# Trigger_Sequencer_build_tested.net
KiCad netlist of a schematic drawn in EAGLE
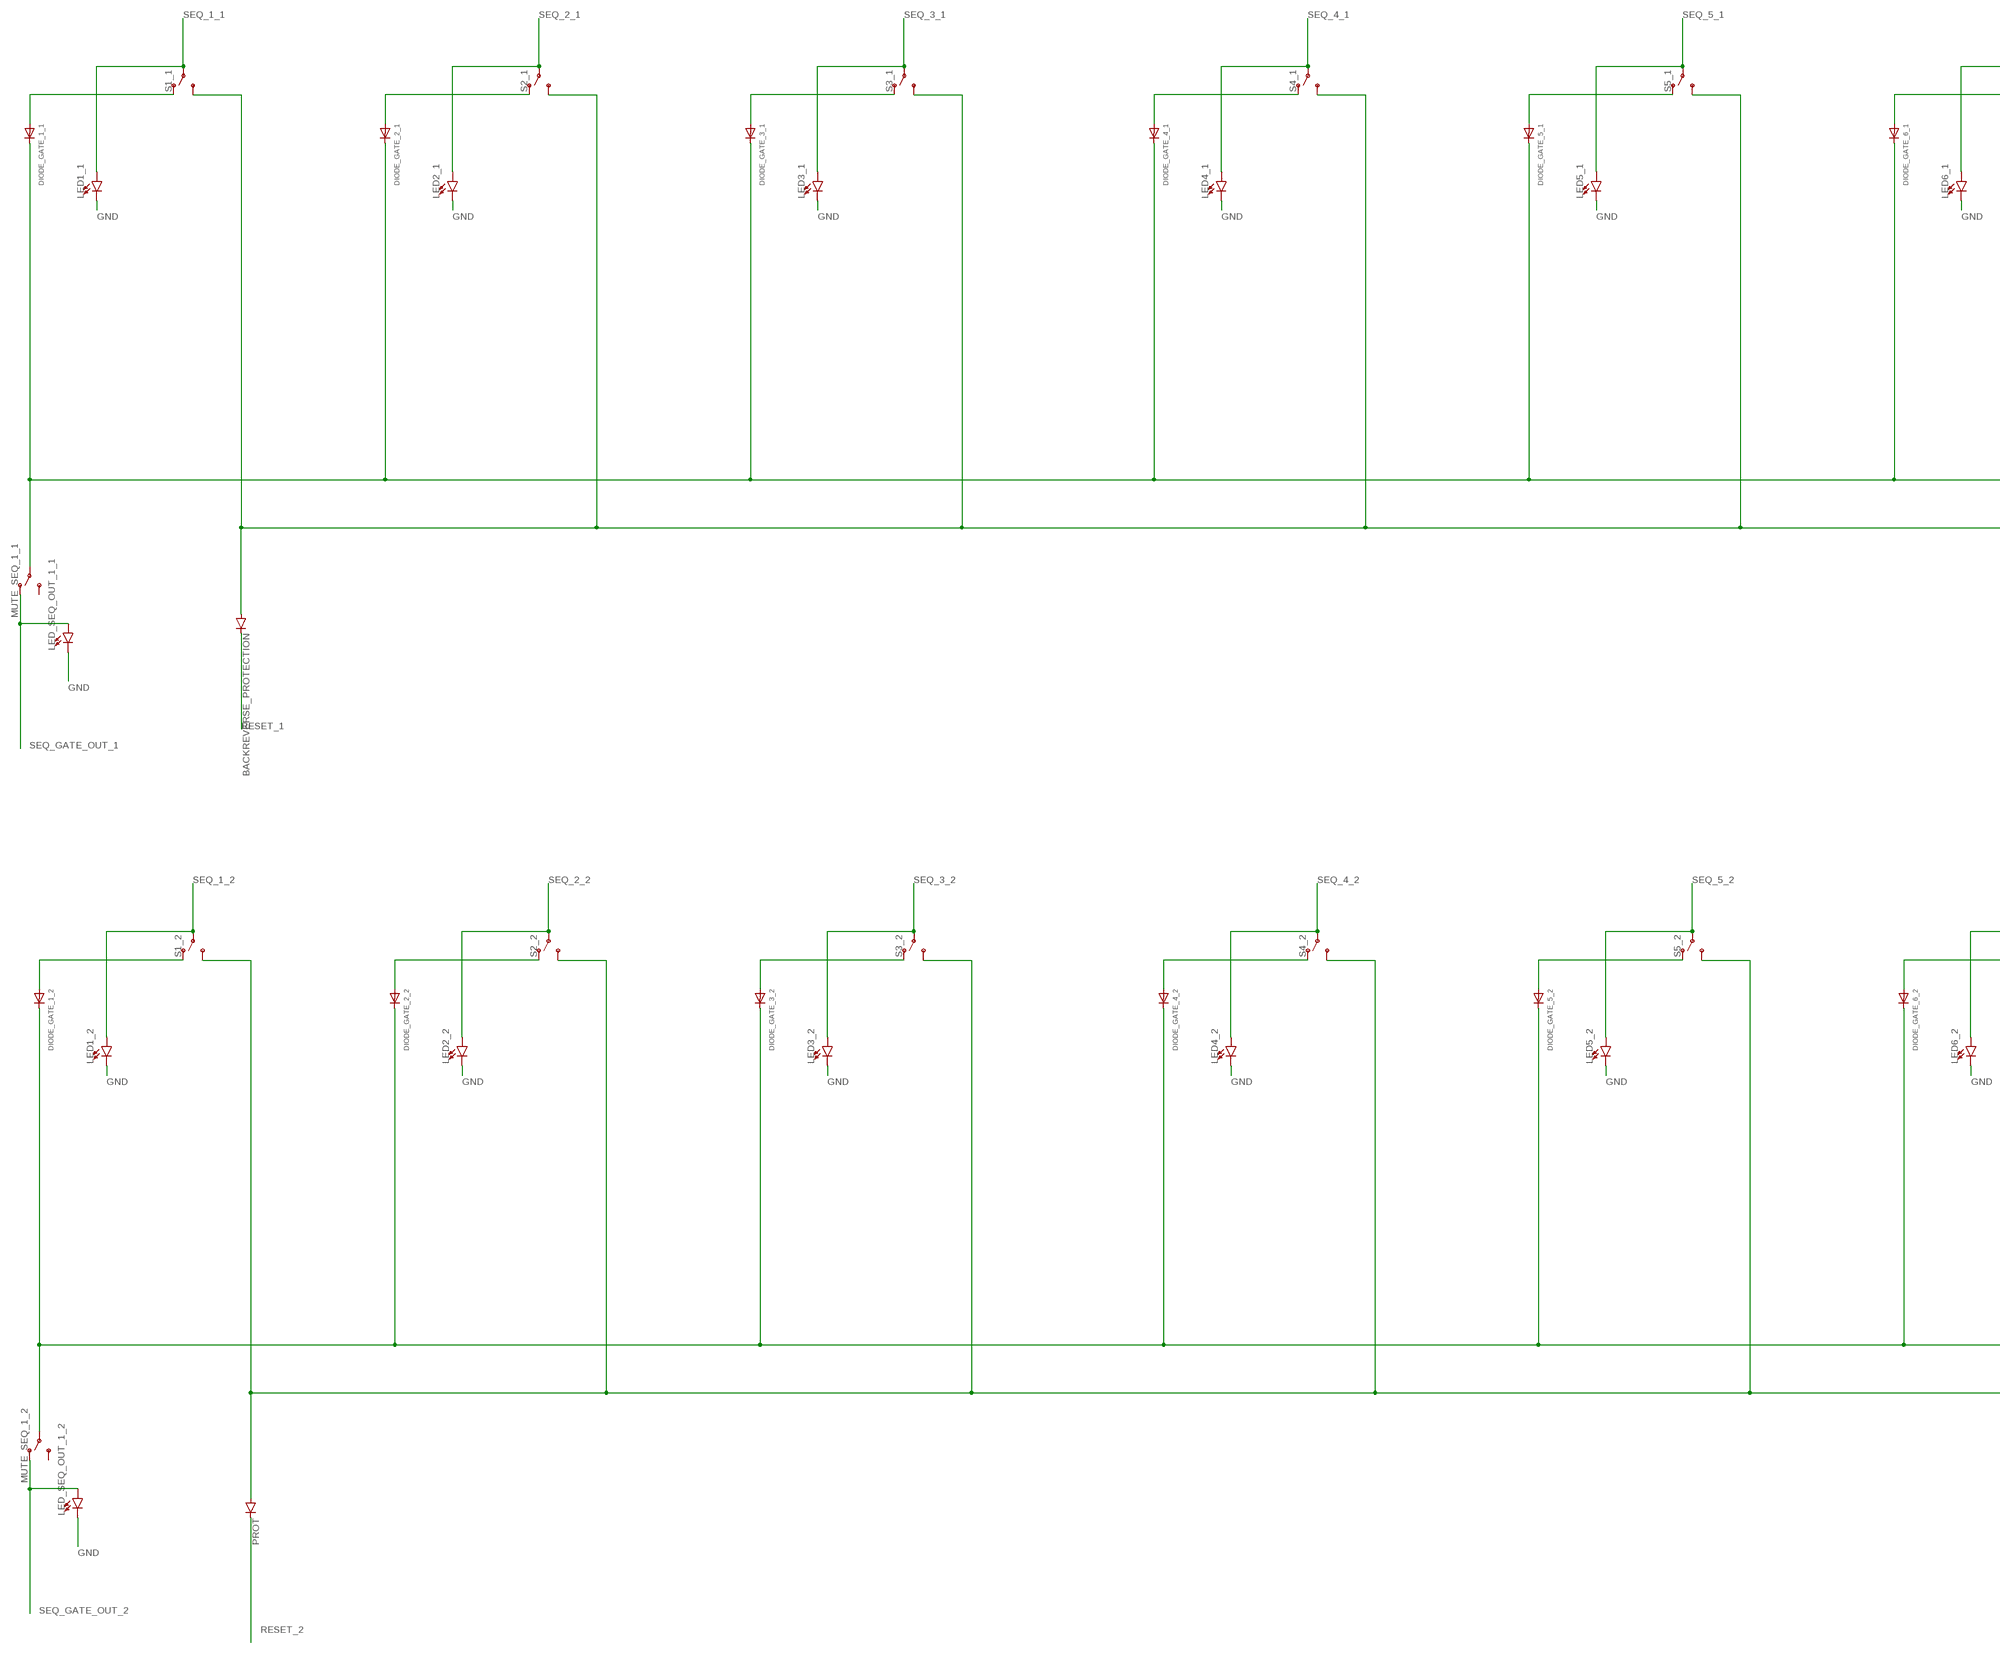
[diagram p0: schematic, sheet 1, part 1 of 2]
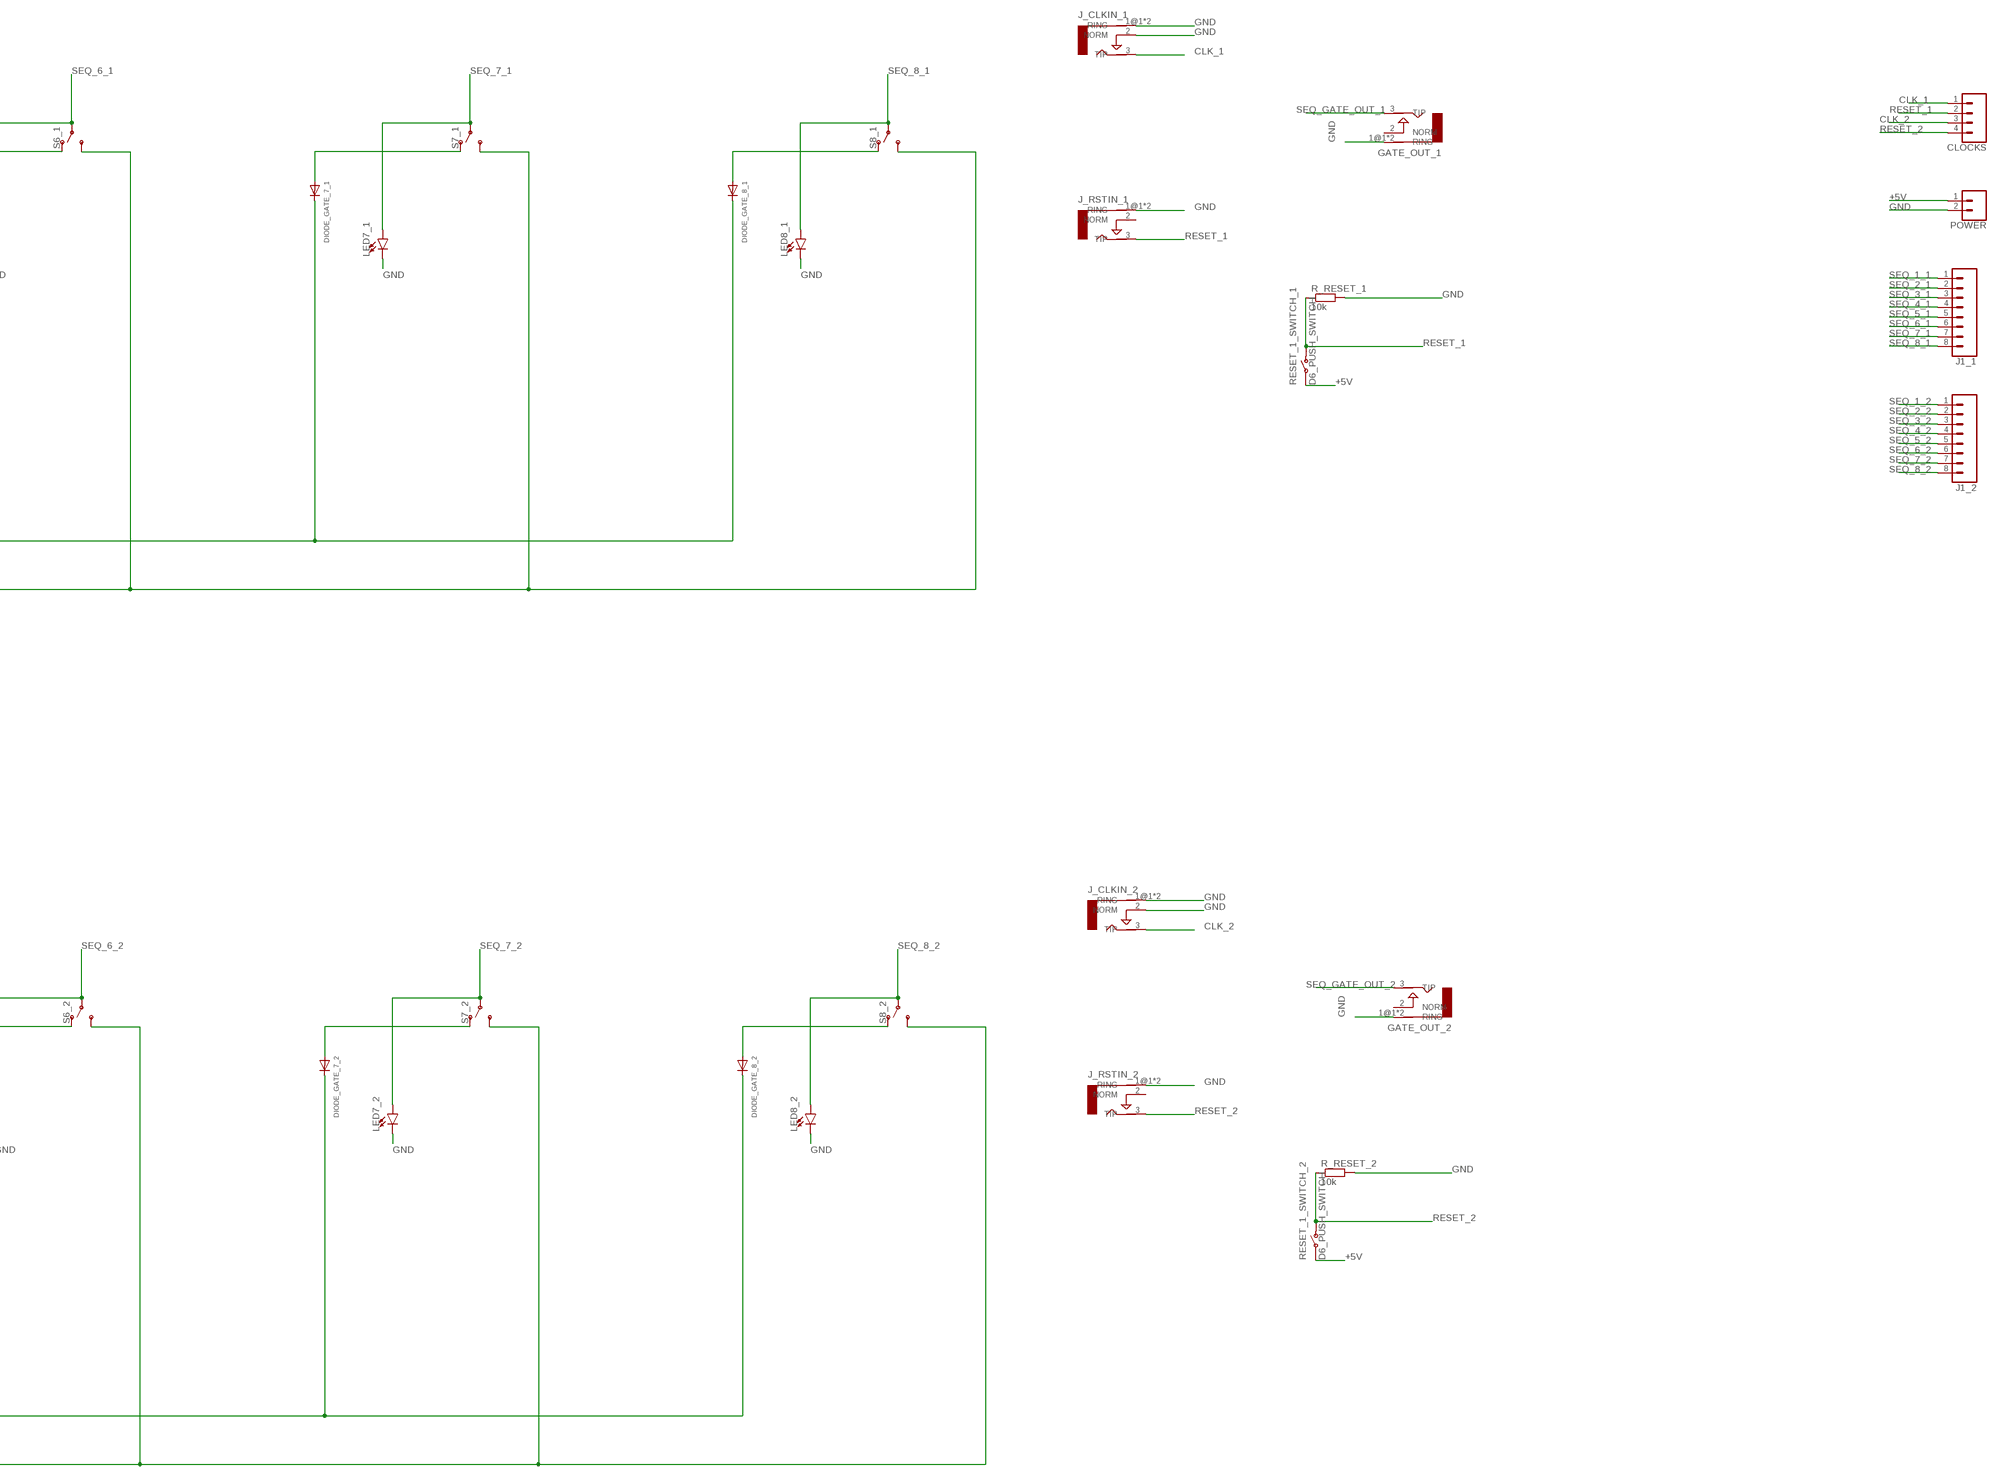
[diagram p1: schematic, sheet 1, part 2 of 2]

(export (version "E")
  (design (tool "Eeschema 10.0.6"))
  (components
    (comp (ref "BACKREVERSE_PROTECTION")
      (value "DIODE1N4148")
      (footprint "eagle-import:DIODE-1N4148")
      (libsource (lib "eagle-import") (part "DIODE1N4148"))
    )
    (comp (ref "CLOCKS")
      (value "CONN_04")
      (footprint "eagle-import:1X04")
      (libsource (lib "eagle-import") (part "CONN_04"))
    )
    (comp (ref "DIODE_GATE_1_1")
      (value "DIODEDO-1N4148")
      (footprint "eagle-import:DO-1N4148")
      (libsource (lib "eagle-import") (part "DIODEDO-1N4148"))
    )
    (comp (ref "DIODE_GATE_1_2")
      (value "DIODEDO-1N4148")
      (footprint "eagle-import:DO-1N4148")
      (libsource (lib "eagle-import") (part "DIODEDO-1N4148"))
    )
    (comp (ref "DIODE_GATE_2_1")
      (value "DIODEDO-1N4148")
      (footprint "eagle-import:DO-1N4148")
      (libsource (lib "eagle-import") (part "DIODEDO-1N4148"))
    )
    (comp (ref "DIODE_GATE_2_2")
      (value "DIODEDO-1N4148")
      (footprint "eagle-import:DO-1N4148")
      (libsource (lib "eagle-import") (part "DIODEDO-1N4148"))
    )
    (comp (ref "DIODE_GATE_3_1")
      (value "DIODEDO-1N4148")
      (footprint "eagle-import:DO-1N4148")
      (libsource (lib "eagle-import") (part "DIODEDO-1N4148"))
    )
    (comp (ref "DIODE_GATE_3_2")
      (value "DIODEDO-1N4148")
      (footprint "eagle-import:DO-1N4148")
      (libsource (lib "eagle-import") (part "DIODEDO-1N4148"))
    )
    (comp (ref "DIODE_GATE_4_1")
      (value "DIODEDO-1N4148")
      (footprint "eagle-import:DO-1N4148")
      (libsource (lib "eagle-import") (part "DIODEDO-1N4148"))
    )
    (comp (ref "DIODE_GATE_4_2")
      (value "DIODEDO-1N4148")
      (footprint "eagle-import:DO-1N4148")
      (libsource (lib "eagle-import") (part "DIODEDO-1N4148"))
    )
    (comp (ref "DIODE_GATE_5_1")
      (value "DIODEDO-1N4148")
      (footprint "eagle-import:DO-1N4148")
      (libsource (lib "eagle-import") (part "DIODEDO-1N4148"))
    )
    (comp (ref "DIODE_GATE_5_2")
      (value "DIODEDO-1N4148")
      (footprint "eagle-import:DO-1N4148")
      (libsource (lib "eagle-import") (part "DIODEDO-1N4148"))
    )
    (comp (ref "DIODE_GATE_6_1")
      (value "DIODEDO-1N4148")
      (footprint "eagle-import:DO-1N4148")
      (libsource (lib "eagle-import") (part "DIODEDO-1N4148"))
    )
    (comp (ref "DIODE_GATE_6_2")
      (value "DIODEDO-1N4148")
      (footprint "eagle-import:DO-1N4148")
      (libsource (lib "eagle-import") (part "DIODEDO-1N4148"))
    )
    (comp (ref "DIODE_GATE_7_1")
      (value "DIODEDO-1N4148")
      (footprint "eagle-import:DO-1N4148")
      (libsource (lib "eagle-import") (part "DIODEDO-1N4148"))
    )
    (comp (ref "DIODE_GATE_7_2")
      (value "DIODEDO-1N4148")
      (footprint "eagle-import:DO-1N4148")
      (libsource (lib "eagle-import") (part "DIODEDO-1N4148"))
    )
    (comp (ref "DIODE_GATE_8_1")
      (value "DIODEDO-1N4148")
      (footprint "eagle-import:DO-1N4148")
      (libsource (lib "eagle-import") (part "DIODEDO-1N4148"))
    )
    (comp (ref "DIODE_GATE_8_2")
      (value "DIODEDO-1N4148")
      (footprint "eagle-import:DO-1N4148")
      (libsource (lib "eagle-import") (part "DIODEDO-1N4148"))
    )
    (comp (ref "GATE_OUT_1")
      (value "AUDIO-JACKERTHENVAR")
      (footprint "eagle-import:ERTHENVAR-JACK")
      (libsource (lib "eagle-import") (part "AUDIO-JACKERTHENVAR"))
    )
    (comp (ref "GATE_OUT_2")
      (value "AUDIO-JACKERTHENVAR")
      (footprint "eagle-import:ERTHENVAR-JACK")
      (libsource (lib "eagle-import") (part "AUDIO-JACKERTHENVAR"))
    )
    (comp (ref "J1_1")
      (value "CONN_08NO_SILK_FEMALE_PTH")
      (footprint "eagle-import:1X08_NO_SILK")
      (libsource (lib "eagle-import") (part "CONN_08NO_SILK_FEMALE_PTH"))
    )
    (comp (ref "J1_2")
      (value "CONN_08NO_SILK_FEMALE_PTH")
      (footprint "eagle-import:1X08_NO_SILK")
      (libsource (lib "eagle-import") (part "CONN_08NO_SILK_FEMALE_PTH"))
    )
    (comp (ref "J_CLKIN_1")
      (value "AUDIO-JACKERTHENVAR")
      (footprint "eagle-import:ERTHENVAR-JACK")
      (libsource (lib "eagle-import") (part "AUDIO-JACKERTHENVAR"))
    )
    (comp (ref "J_CLKIN_2")
      (value "AUDIO-JACKERTHENVAR")
      (footprint "eagle-import:ERTHENVAR-JACK")
      (libsource (lib "eagle-import") (part "AUDIO-JACKERTHENVAR"))
    )
    (comp (ref "J_RSTIN_1")
      (value "AUDIO-JACKERTHENVAR")
      (footprint "eagle-import:ERTHENVAR-JACK")
      (libsource (lib "eagle-import") (part "AUDIO-JACKERTHENVAR"))
    )
    (comp (ref "J_RSTIN_2")
      (value "AUDIO-JACKERTHENVAR")
      (footprint "eagle-import:ERTHENVAR-JACK")
      (libsource (lib "eagle-import") (part "AUDIO-JACKERTHENVAR"))
    )
    (comp (ref "LED1_1")
      (value "LED-3MM-NO_SILK")
      (footprint "eagle-import:LED_3MM-NS")
      (libsource (lib "eagle-import") (part "LED-3MM-NO_SILK"))
    )
    (comp (ref "LED1_2")
      (value "LED-3MM-NO_SILK")
      (footprint "eagle-import:LED_3MM-NS")
      (libsource (lib "eagle-import") (part "LED-3MM-NO_SILK"))
    )
    (comp (ref "LED2_1")
      (value "LED-3MM-NO_SILK")
      (footprint "eagle-import:LED_3MM-NS")
      (libsource (lib "eagle-import") (part "LED-3MM-NO_SILK"))
    )
    (comp (ref "LED2_2")
      (value "LED-3MM-NO_SILK")
      (footprint "eagle-import:LED_3MM-NS")
      (libsource (lib "eagle-import") (part "LED-3MM-NO_SILK"))
    )
    (comp (ref "LED3_1")
      (value "LED-3MM-NO_SILK")
      (footprint "eagle-import:LED_3MM-NS")
      (libsource (lib "eagle-import") (part "LED-3MM-NO_SILK"))
    )
    (comp (ref "LED3_2")
      (value "LED-3MM-NO_SILK")
      (footprint "eagle-import:LED_3MM-NS")
      (libsource (lib "eagle-import") (part "LED-3MM-NO_SILK"))
    )
    (comp (ref "LED4_1")
      (value "LED-3MM-NO_SILK")
      (footprint "eagle-import:LED_3MM-NS")
      (libsource (lib "eagle-import") (part "LED-3MM-NO_SILK"))
    )
    (comp (ref "LED4_2")
      (value "LED-3MM-NO_SILK")
      (footprint "eagle-import:LED_3MM-NS")
      (libsource (lib "eagle-import") (part "LED-3MM-NO_SILK"))
    )
    (comp (ref "LED5_1")
      (value "LED-3MM-NO_SILK")
      (footprint "eagle-import:LED_3MM-NS")
      (libsource (lib "eagle-import") (part "LED-3MM-NO_SILK"))
    )
    (comp (ref "LED5_2")
      (value "LED-3MM-NO_SILK")
      (footprint "eagle-import:LED_3MM-NS")
      (libsource (lib "eagle-import") (part "LED-3MM-NO_SILK"))
    )
    (comp (ref "LED6_1")
      (value "LED-3MM-NO_SILK")
      (footprint "eagle-import:LED_3MM-NS")
      (libsource (lib "eagle-import") (part "LED-3MM-NO_SILK"))
    )
    (comp (ref "LED6_2")
      (value "LED-3MM-NO_SILK")
      (footprint "eagle-import:LED_3MM-NS")
      (libsource (lib "eagle-import") (part "LED-3MM-NO_SILK"))
    )
    (comp (ref "LED7_1")
      (value "LED-3MM-NO_SILK")
      (footprint "eagle-import:LED_3MM-NS")
      (libsource (lib "eagle-import") (part "LED-3MM-NO_SILK"))
    )
    (comp (ref "LED7_2")
      (value "LED-3MM-NO_SILK")
      (footprint "eagle-import:LED_3MM-NS")
      (libsource (lib "eagle-import") (part "LED-3MM-NO_SILK"))
    )
    (comp (ref "LED8_1")
      (value "LED-3MM-NO_SILK")
      (footprint "eagle-import:LED_3MM-NS")
      (libsource (lib "eagle-import") (part "LED-3MM-NO_SILK"))
    )
    (comp (ref "LED8_2")
      (value "LED-3MM-NO_SILK")
      (footprint "eagle-import:LED_3MM-NS")
      (libsource (lib "eagle-import") (part "LED-3MM-NO_SILK"))
    )
    (comp (ref "LED_SEQ_OUT_1_1")
      (value "LED-3MM-NO_SILK")
      (footprint "eagle-import:LED_3MM-NS")
      (libsource (lib "eagle-import") (part "LED-3MM-NO_SILK"))
    )
    (comp (ref "LED_SEQ_OUT_1_2")
      (value "LED-3MM-NO_SILK")
      (footprint "eagle-import:LED_3MM-NS")
      (libsource (lib "eagle-import") (part "LED-3MM-NO_SILK"))
    )
    (comp (ref "MUTE_SEQ_1_1")
      (value "SWITCH-SPDT-PTH-11.6X4.0MM")
      (footprint "eagle-import:SWITCH_SPDT_PTH_11.6X4.0MM")
      (libsource (lib "eagle-import") (part "SWITCH-SPDT-PTH-11.6X4.0MM"))
    )
    (comp (ref "MUTE_SEQ_1_2")
      (value "SWITCH-SPDT-PTH-11.6X4.0MM")
      (footprint "eagle-import:SWITCH_SPDT_PTH_11.6X4.0MM")
      (libsource (lib "eagle-import") (part "SWITCH-SPDT-PTH-11.6X4.0MM"))
    )
    (comp (ref "POWER")
      (value "CONN_02")
      (footprint "eagle-import:1X02")
      (libsource (lib "eagle-import") (part "CONN_02"))
    )
    (comp (ref "PROT")
      (value "DIODE1N4148")
      (footprint "eagle-import:DIODE-1N4148")
      (libsource (lib "eagle-import") (part "DIODE1N4148"))
    )
    (comp (ref "RESET_1_SWITCH_1")
      (value "D6_PUSH_SWITCH")
      (footprint "eagle-import:D6_PUSH_SWITCH")
      (libsource (lib "eagle-import") (part "D6_PUSH_SWITCH"))
    )
    (comp (ref "RESET_1_SWITCH_2")
      (value "D6_PUSH_SWITCH")
      (footprint "eagle-import:D6_PUSH_SWITCH")
      (libsource (lib "eagle-import") (part "D6_PUSH_SWITCH"))
    )
    (comp (ref "R_RESET_1")
      (value "10k")
      (footprint "eagle-import:VERTICAL_RESISTOR")
      (libsource (lib "eagle-import") (part "RESISTORVERTICAL"))
    )
    (comp (ref "R_RESET_2")
      (value "10k")
      (footprint "eagle-import:VERTICAL_RESISTOR")
      (libsource (lib "eagle-import") (part "RESISTORVERTICAL"))
    )
    (comp (ref "S1_1")
      (value "SWITCH-SPDT-PTH-11.6X4.0MM")
      (footprint "eagle-import:SWITCH_SPDT_PTH_11.6X4.0MM")
      (libsource (lib "eagle-import") (part "SWITCH-SPDT-PTH-11.6X4.0MM"))
    )
    (comp (ref "S1_2")
      (value "SWITCH-SPDT-PTH-11.6X4.0MM")
      (footprint "eagle-import:SWITCH_SPDT_PTH_11.6X4.0MM")
      (libsource (lib "eagle-import") (part "SWITCH-SPDT-PTH-11.6X4.0MM"))
    )
    (comp (ref "S2_1")
      (value "SWITCH-SPDT-PTH-11.6X4.0MM")
      (footprint "eagle-import:SWITCH_SPDT_PTH_11.6X4.0MM")
      (libsource (lib "eagle-import") (part "SWITCH-SPDT-PTH-11.6X4.0MM"))
    )
    (comp (ref "S2_2")
      (value "SWITCH-SPDT-PTH-11.6X4.0MM")
      (footprint "eagle-import:SWITCH_SPDT_PTH_11.6X4.0MM")
      (libsource (lib "eagle-import") (part "SWITCH-SPDT-PTH-11.6X4.0MM"))
    )
    (comp (ref "S3_1")
      (value "SWITCH-SPDT-PTH-11.6X4.0MM")
      (footprint "eagle-import:SWITCH_SPDT_PTH_11.6X4.0MM")
      (libsource (lib "eagle-import") (part "SWITCH-SPDT-PTH-11.6X4.0MM"))
    )
    (comp (ref "S3_2")
      (value "SWITCH-SPDT-PTH-11.6X4.0MM")
      (footprint "eagle-import:SWITCH_SPDT_PTH_11.6X4.0MM")
      (libsource (lib "eagle-import") (part "SWITCH-SPDT-PTH-11.6X4.0MM"))
    )
    (comp (ref "S4_1")
      (value "SWITCH-SPDT-PTH-11.6X4.0MM")
      (footprint "eagle-import:SWITCH_SPDT_PTH_11.6X4.0MM")
      (libsource (lib "eagle-import") (part "SWITCH-SPDT-PTH-11.6X4.0MM"))
    )
    (comp (ref "S4_2")
      (value "SWITCH-SPDT-PTH-11.6X4.0MM")
      (footprint "eagle-import:SWITCH_SPDT_PTH_11.6X4.0MM")
      (libsource (lib "eagle-import") (part "SWITCH-SPDT-PTH-11.6X4.0MM"))
    )
    (comp (ref "S5_1")
      (value "SWITCH-SPDT-PTH-11.6X4.0MM")
      (footprint "eagle-import:SWITCH_SPDT_PTH_11.6X4.0MM")
      (libsource (lib "eagle-import") (part "SWITCH-SPDT-PTH-11.6X4.0MM"))
    )
    (comp (ref "S5_2")
      (value "SWITCH-SPDT-PTH-11.6X4.0MM")
      (footprint "eagle-import:SWITCH_SPDT_PTH_11.6X4.0MM")
      (libsource (lib "eagle-import") (part "SWITCH-SPDT-PTH-11.6X4.0MM"))
    )
    (comp (ref "S6_1")
      (value "SWITCH-SPDT-PTH-11.6X4.0MM")
      (footprint "eagle-import:SWITCH_SPDT_PTH_11.6X4.0MM")
      (libsource (lib "eagle-import") (part "SWITCH-SPDT-PTH-11.6X4.0MM"))
    )
    (comp (ref "S6_2")
      (value "SWITCH-SPDT-PTH-11.6X4.0MM")
      (footprint "eagle-import:SWITCH_SPDT_PTH_11.6X4.0MM")
      (libsource (lib "eagle-import") (part "SWITCH-SPDT-PTH-11.6X4.0MM"))
    )
    (comp (ref "S7_1")
      (value "SWITCH-SPDT-PTH-11.6X4.0MM")
      (footprint "eagle-import:SWITCH_SPDT_PTH_11.6X4.0MM")
      (libsource (lib "eagle-import") (part "SWITCH-SPDT-PTH-11.6X4.0MM"))
    )
    (comp (ref "S7_2")
      (value "SWITCH-SPDT-PTH-11.6X4.0MM")
      (footprint "eagle-import:SWITCH_SPDT_PTH_11.6X4.0MM")
      (libsource (lib "eagle-import") (part "SWITCH-SPDT-PTH-11.6X4.0MM"))
    )
    (comp (ref "S8_1")
      (value "SWITCH-SPDT-PTH-11.6X4.0MM")
      (footprint "eagle-import:SWITCH_SPDT_PTH_11.6X4.0MM")
      (libsource (lib "eagle-import") (part "SWITCH-SPDT-PTH-11.6X4.0MM"))
    )
    (comp (ref "S8_2")
      (value "SWITCH-SPDT-PTH-11.6X4.0MM")
      (footprint "eagle-import:SWITCH_SPDT_PTH_11.6X4.0MM")
      (libsource (lib "eagle-import") (part "SWITCH-SPDT-PTH-11.6X4.0MM"))
    )
  )
  (nets
    (net (code "1") (name "/+5V") (class "Default")
      (node (ref "POWER") (pin "1") (pinfunction "1_1") (pintype "passive"))
      (node (ref "RESET_1_SWITCH_1") (pin "P$3") (pinfunction "P_P$3") (pintype "passive"))
      (node (ref "RESET_1_SWITCH_1") (pin "P$4") (pinfunction "P_P$4") (pintype "passive"))
      (node (ref "RESET_1_SWITCH_2") (pin "P$3") (pinfunction "P_P$3") (pintype "passive"))
      (node (ref "RESET_1_SWITCH_2") (pin "P$4") (pinfunction "P_P$4") (pintype "passive"))
    )
    (net (code "2") (name "/CLK_1") (class "Default")
      (node (ref "CLOCKS") (pin "1") (pinfunction "1_1") (pintype "passive"))
      (node (ref "J_CLKIN_1") (pin "3") (pinfunction "TIP_3") (pintype "bidirectional"))
    )
    (net (code "3") (name "/CLK_2") (class "Default")
      (node (ref "CLOCKS") (pin "3") (pinfunction "3_3") (pintype "passive"))
      (node (ref "J_CLKIN_2") (pin "3") (pinfunction "TIP_3") (pintype "bidirectional"))
    )
    (net (code "4") (name "/GND") (class "Default")
      (node (ref "GATE_OUT_1") (pin "1@1") (pinfunction "RING_1@1") (pintype "bidirectional"))
      (node (ref "GATE_OUT_1") (pin "1@2") (pinfunction "RING_1@2") (pintype "bidirectional"))
      (node (ref "GATE_OUT_2") (pin "1@1") (pinfunction "RING_1@1") (pintype "bidirectional"))
      (node (ref "GATE_OUT_2") (pin "1@2") (pinfunction "RING_1@2") (pintype "bidirectional"))
      (node (ref "J_CLKIN_1") (pin "1@1") (pinfunction "RING_1@1") (pintype "bidirectional"))
      (node (ref "J_CLKIN_1") (pin "1@2") (pinfunction "RING_1@2") (pintype "bidirectional"))
      (node (ref "J_CLKIN_1") (pin "2") (pinfunction "NORM_2") (pintype "bidirectional"))
      (node (ref "J_CLKIN_2") (pin "1@1") (pinfunction "RING_1@1") (pintype "bidirectional"))
      (node (ref "J_CLKIN_2") (pin "1@2") (pinfunction "RING_1@2") (pintype "bidirectional"))
      (node (ref "J_CLKIN_2") (pin "2") (pinfunction "NORM_2") (pintype "bidirectional"))
      (node (ref "J_RSTIN_1") (pin "1@1") (pinfunction "RING_1@1") (pintype "bidirectional"))
      (node (ref "J_RSTIN_1") (pin "1@2") (pinfunction "RING_1@2") (pintype "bidirectional"))
      (node (ref "J_RSTIN_2") (pin "1@1") (pinfunction "RING_1@1") (pintype "bidirectional"))
      (node (ref "J_RSTIN_2") (pin "1@2") (pinfunction "RING_1@2") (pintype "bidirectional"))
      (node (ref "LED1_1") (pin "K") (pinfunction "C_K") (pintype "passive"))
      (node (ref "LED1_2") (pin "K") (pinfunction "C_K") (pintype "passive"))
      (node (ref "LED2_1") (pin "K") (pinfunction "C_K") (pintype "passive"))
      (node (ref "LED2_2") (pin "K") (pinfunction "C_K") (pintype "passive"))
      (node (ref "LED3_1") (pin "K") (pinfunction "C_K") (pintype "passive"))
      (node (ref "LED3_2") (pin "K") (pinfunction "C_K") (pintype "passive"))
      (node (ref "LED4_1") (pin "K") (pinfunction "C_K") (pintype "passive"))
      (node (ref "LED4_2") (pin "K") (pinfunction "C_K") (pintype "passive"))
      (node (ref "LED5_1") (pin "K") (pinfunction "C_K") (pintype "passive"))
      (node (ref "LED5_2") (pin "K") (pinfunction "C_K") (pintype "passive"))
      (node (ref "LED6_1") (pin "K") (pinfunction "C_K") (pintype "passive"))
      (node (ref "LED6_2") (pin "K") (pinfunction "C_K") (pintype "passive"))
      (node (ref "LED7_1") (pin "K") (pinfunction "C_K") (pintype "passive"))
      (node (ref "LED7_2") (pin "K") (pinfunction "C_K") (pintype "passive"))
      (node (ref "LED8_1") (pin "K") (pinfunction "C_K") (pintype "passive"))
      (node (ref "LED8_2") (pin "K") (pinfunction "C_K") (pintype "passive"))
      (node (ref "LED_SEQ_OUT_1_1") (pin "K") (pinfunction "C_K") (pintype "passive"))
      (node (ref "LED_SEQ_OUT_1_2") (pin "K") (pinfunction "C_K") (pintype "passive"))
      (node (ref "POWER") (pin "2") (pinfunction "2_2") (pintype "passive"))
      (node (ref "R_RESET_1") (pin "2") (pinfunction "2_2") (pintype "passive"))
      (node (ref "R_RESET_2") (pin "2") (pinfunction "2_2") (pintype "passive"))
    )
    (net (code "5") (name "/RESET_1") (class "Default")
      (node (ref "BACKREVERSE_PROTECTION") (pin "A") (pinfunction "A_A") (pintype "passive"))
      (node (ref "BACKREVERSE_PROTECTION") (pin "C") (pinfunction "C_C") (pintype "passive"))
      (node (ref "CLOCKS") (pin "2") (pinfunction "2_2") (pintype "passive"))
      (node (ref "J_RSTIN_1") (pin "3") (pinfunction "TIP_3") (pintype "bidirectional"))
      (node (ref "RESET_1_SWITCH_1") (pin "P$1") (pinfunction "O_P$1") (pintype "passive"))
      (node (ref "RESET_1_SWITCH_1") (pin "P$2") (pinfunction "O_P$2") (pintype "passive"))
      (node (ref "R_RESET_1") (pin "1") (pinfunction "1_1") (pintype "passive"))
      (node (ref "S1_1") (pin "3") (pinfunction "S_3") (pintype "passive"))
      (node (ref "S2_1") (pin "3") (pinfunction "S_3") (pintype "passive"))
      (node (ref "S3_1") (pin "3") (pinfunction "S_3") (pintype "passive"))
      (node (ref "S4_1") (pin "3") (pinfunction "S_3") (pintype "passive"))
      (node (ref "S5_1") (pin "3") (pinfunction "S_3") (pintype "passive"))
      (node (ref "S6_1") (pin "3") (pinfunction "S_3") (pintype "passive"))
      (node (ref "S7_1") (pin "3") (pinfunction "S_3") (pintype "passive"))
      (node (ref "S8_1") (pin "3") (pinfunction "S_3") (pintype "passive"))
    )
    (net (code "6") (name "/RESET_2") (class "Default")
      (node (ref "CLOCKS") (pin "4") (pinfunction "4_4") (pintype "passive"))
      (node (ref "J_RSTIN_2") (pin "3") (pinfunction "TIP_3") (pintype "bidirectional"))
      (node (ref "PROT") (pin "A") (pinfunction "A_A") (pintype "passive"))
      (node (ref "PROT") (pin "C") (pinfunction "C_C") (pintype "passive"))
      (node (ref "RESET_1_SWITCH_2") (pin "P$1") (pinfunction "O_P$1") (pintype "passive"))
      (node (ref "RESET_1_SWITCH_2") (pin "P$2") (pinfunction "O_P$2") (pintype "passive"))
      (node (ref "R_RESET_2") (pin "1") (pinfunction "1_1") (pintype "passive"))
      (node (ref "S1_2") (pin "3") (pinfunction "S_3") (pintype "passive"))
      (node (ref "S2_2") (pin "3") (pinfunction "S_3") (pintype "passive"))
      (node (ref "S3_2") (pin "3") (pinfunction "S_3") (pintype "passive"))
      (node (ref "S4_2") (pin "3") (pinfunction "S_3") (pintype "passive"))
      (node (ref "S5_2") (pin "3") (pinfunction "S_3") (pintype "passive"))
      (node (ref "S6_2") (pin "3") (pinfunction "S_3") (pintype "passive"))
      (node (ref "S7_2") (pin "3") (pinfunction "S_3") (pintype "passive"))
      (node (ref "S8_2") (pin "3") (pinfunction "S_3") (pintype "passive"))
    )
    (net (code "7") (name "/SEQ_1_1") (class "Default")
      (node (ref "J1_1") (pin "1") (pinfunction "1_1") (pintype "passive"))
      (node (ref "LED1_1") (pin "A") (pinfunction "A_A") (pintype "passive"))
      (node (ref "S1_1") (pin "2") (pinfunction "P_2") (pintype "passive"))
    )
    (net (code "8") (name "/SEQ_1_2") (class "Default")
      (node (ref "J1_2") (pin "1") (pinfunction "1_1") (pintype "passive"))
      (node (ref "LED1_2") (pin "A") (pinfunction "A_A") (pintype "passive"))
      (node (ref "S1_2") (pin "2") (pinfunction "P_2") (pintype "passive"))
    )
    (net (code "9") (name "/SEQ_2_1") (class "Default")
      (node (ref "J1_1") (pin "2") (pinfunction "2_2") (pintype "passive"))
      (node (ref "LED2_1") (pin "A") (pinfunction "A_A") (pintype "passive"))
      (node (ref "S2_1") (pin "2") (pinfunction "P_2") (pintype "passive"))
    )
    (net (code "10") (name "/SEQ_2_2") (class "Default")
      (node (ref "J1_2") (pin "2") (pinfunction "2_2") (pintype "passive"))
      (node (ref "LED2_2") (pin "A") (pinfunction "A_A") (pintype "passive"))
      (node (ref "S2_2") (pin "2") (pinfunction "P_2") (pintype "passive"))
    )
    (net (code "11") (name "/SEQ_3_1") (class "Default")
      (node (ref "J1_1") (pin "3") (pinfunction "3_3") (pintype "passive"))
      (node (ref "LED3_1") (pin "A") (pinfunction "A_A") (pintype "passive"))
      (node (ref "S3_1") (pin "2") (pinfunction "P_2") (pintype "passive"))
    )
    (net (code "12") (name "/SEQ_3_2") (class "Default")
      (node (ref "J1_2") (pin "3") (pinfunction "3_3") (pintype "passive"))
      (node (ref "LED3_2") (pin "A") (pinfunction "A_A") (pintype "passive"))
      (node (ref "S3_2") (pin "2") (pinfunction "P_2") (pintype "passive"))
    )
    (net (code "13") (name "/SEQ_4_1") (class "Default")
      (node (ref "J1_1") (pin "4") (pinfunction "4_4") (pintype "passive"))
      (node (ref "LED4_1") (pin "A") (pinfunction "A_A") (pintype "passive"))
      (node (ref "S4_1") (pin "2") (pinfunction "P_2") (pintype "passive"))
    )
    (net (code "14") (name "/SEQ_4_2") (class "Default")
      (node (ref "J1_2") (pin "4") (pinfunction "4_4") (pintype "passive"))
      (node (ref "LED4_2") (pin "A") (pinfunction "A_A") (pintype "passive"))
      (node (ref "S4_2") (pin "2") (pinfunction "P_2") (pintype "passive"))
    )
    (net (code "15") (name "/SEQ_5_1") (class "Default")
      (node (ref "J1_1") (pin "5") (pinfunction "5_5") (pintype "passive"))
      (node (ref "LED5_1") (pin "A") (pinfunction "A_A") (pintype "passive"))
      (node (ref "S5_1") (pin "2") (pinfunction "P_2") (pintype "passive"))
    )
    (net (code "16") (name "/SEQ_5_2") (class "Default")
      (node (ref "J1_2") (pin "5") (pinfunction "5_5") (pintype "passive"))
      (node (ref "LED5_2") (pin "A") (pinfunction "A_A") (pintype "passive"))
      (node (ref "S5_2") (pin "2") (pinfunction "P_2") (pintype "passive"))
    )
    (net (code "17") (name "/SEQ_6_1") (class "Default")
      (node (ref "J1_1") (pin "6") (pinfunction "6_6") (pintype "passive"))
      (node (ref "LED6_1") (pin "A") (pinfunction "A_A") (pintype "passive"))
      (node (ref "S6_1") (pin "2") (pinfunction "P_2") (pintype "passive"))
    )
    (net (code "18") (name "/SEQ_6_2") (class "Default")
      (node (ref "J1_2") (pin "6") (pinfunction "6_6") (pintype "passive"))
      (node (ref "LED6_2") (pin "A") (pinfunction "A_A") (pintype "passive"))
      (node (ref "S6_2") (pin "2") (pinfunction "P_2") (pintype "passive"))
    )
    (net (code "19") (name "/SEQ_7_1") (class "Default")
      (node (ref "J1_1") (pin "7") (pinfunction "7_7") (pintype "passive"))
      (node (ref "LED7_1") (pin "A") (pinfunction "A_A") (pintype "passive"))
      (node (ref "S7_1") (pin "2") (pinfunction "P_2") (pintype "passive"))
    )
    (net (code "20") (name "/SEQ_7_2") (class "Default")
      (node (ref "J1_2") (pin "7") (pinfunction "7_7") (pintype "passive"))
      (node (ref "LED7_2") (pin "A") (pinfunction "A_A") (pintype "passive"))
      (node (ref "S7_2") (pin "2") (pinfunction "P_2") (pintype "passive"))
    )
    (net (code "21") (name "/SEQ_8_1") (class "Default")
      (node (ref "J1_1") (pin "8") (pinfunction "8_8") (pintype "passive"))
      (node (ref "LED8_1") (pin "A") (pinfunction "A_A") (pintype "passive"))
      (node (ref "S8_1") (pin "2") (pinfunction "P_2") (pintype "passive"))
    )
    (net (code "22") (name "/SEQ_8_2") (class "Default")
      (node (ref "J1_2") (pin "8") (pinfunction "8_8") (pintype "passive"))
      (node (ref "LED8_2") (pin "A") (pinfunction "A_A") (pintype "passive"))
      (node (ref "S8_2") (pin "2") (pinfunction "P_2") (pintype "passive"))
    )
    (net (code "23") (name "/SEQ_GATE_OUT_1") (class "Default")
      (node (ref "GATE_OUT_1") (pin "3") (pinfunction "TIP_3") (pintype "bidirectional"))
      (node (ref "LED_SEQ_OUT_1_1") (pin "A") (pinfunction "A_A") (pintype "passive"))
      (node (ref "MUTE_SEQ_1_1") (pin "1") (pinfunction "O_1") (pintype "passive"))
    )
    (net (code "24") (name "/SEQ_GATE_OUT_2") (class "Default")
      (node (ref "GATE_OUT_2") (pin "3") (pinfunction "TIP_3") (pintype "bidirectional"))
      (node (ref "LED_SEQ_OUT_1_2") (pin "A") (pinfunction "A_A") (pintype "passive"))
      (node (ref "MUTE_SEQ_1_2") (pin "1") (pinfunction "O_1") (pintype "passive"))
    )
    (net (code "25") (name "Net-(MUTE_SEQ_1_1-P)") (class "Default")
      (node (ref "DIODE_GATE_1_1") (pin "C") (pinfunction "C_C") (pintype "passive"))
      (node (ref "DIODE_GATE_2_1") (pin "C") (pinfunction "C_C") (pintype "passive"))
      (node (ref "DIODE_GATE_3_1") (pin "C") (pinfunction "C_C") (pintype "passive"))
      (node (ref "DIODE_GATE_4_1") (pin "C") (pinfunction "C_C") (pintype "passive"))
      (node (ref "DIODE_GATE_5_1") (pin "C") (pinfunction "C_C") (pintype "passive"))
      (node (ref "DIODE_GATE_6_1") (pin "C") (pinfunction "C_C") (pintype "passive"))
      (node (ref "DIODE_GATE_7_1") (pin "C") (pinfunction "C_C") (pintype "passive"))
      (node (ref "DIODE_GATE_8_1") (pin "C") (pinfunction "C_C") (pintype "passive"))
      (node (ref "MUTE_SEQ_1_1") (pin "2") (pinfunction "P_2") (pintype "passive"))
    )
    (net (code "26") (name "Net-(MUTE_SEQ_1_2-P)") (class "Default")
      (node (ref "DIODE_GATE_1_2") (pin "C") (pinfunction "C_C") (pintype "passive"))
      (node (ref "DIODE_GATE_2_2") (pin "C") (pinfunction "C_C") (pintype "passive"))
      (node (ref "DIODE_GATE_3_2") (pin "C") (pinfunction "C_C") (pintype "passive"))
      (node (ref "DIODE_GATE_4_2") (pin "C") (pinfunction "C_C") (pintype "passive"))
      (node (ref "DIODE_GATE_5_2") (pin "C") (pinfunction "C_C") (pintype "passive"))
      (node (ref "DIODE_GATE_6_2") (pin "C") (pinfunction "C_C") (pintype "passive"))
      (node (ref "DIODE_GATE_7_2") (pin "C") (pinfunction "C_C") (pintype "passive"))
      (node (ref "DIODE_GATE_8_2") (pin "C") (pinfunction "C_C") (pintype "passive"))
      (node (ref "MUTE_SEQ_1_2") (pin "2") (pinfunction "P_2") (pintype "passive"))
    )
    (net (code "27") (name "Net-(S1_1-O)") (class "Default")
      (node (ref "DIODE_GATE_1_1") (pin "A") (pinfunction "A_A") (pintype "passive"))
      (node (ref "S1_1") (pin "1") (pinfunction "O_1") (pintype "passive"))
    )
    (net (code "28") (name "Net-(S1_2-O)") (class "Default")
      (node (ref "DIODE_GATE_1_2") (pin "A") (pinfunction "A_A") (pintype "passive"))
      (node (ref "S1_2") (pin "1") (pinfunction "O_1") (pintype "passive"))
    )
    (net (code "29") (name "Net-(S2_1-O)") (class "Default")
      (node (ref "DIODE_GATE_2_1") (pin "A") (pinfunction "A_A") (pintype "passive"))
      (node (ref "S2_1") (pin "1") (pinfunction "O_1") (pintype "passive"))
    )
    (net (code "30") (name "Net-(S2_2-O)") (class "Default")
      (node (ref "DIODE_GATE_2_2") (pin "A") (pinfunction "A_A") (pintype "passive"))
      (node (ref "S2_2") (pin "1") (pinfunction "O_1") (pintype "passive"))
    )
    (net (code "31") (name "Net-(S3_1-O)") (class "Default")
      (node (ref "DIODE_GATE_3_1") (pin "A") (pinfunction "A_A") (pintype "passive"))
      (node (ref "S3_1") (pin "1") (pinfunction "O_1") (pintype "passive"))
    )
    (net (code "32") (name "Net-(S3_2-O)") (class "Default")
      (node (ref "DIODE_GATE_3_2") (pin "A") (pinfunction "A_A") (pintype "passive"))
      (node (ref "S3_2") (pin "1") (pinfunction "O_1") (pintype "passive"))
    )
    (net (code "33") (name "Net-(S4_1-O)") (class "Default")
      (node (ref "DIODE_GATE_4_1") (pin "A") (pinfunction "A_A") (pintype "passive"))
      (node (ref "S4_1") (pin "1") (pinfunction "O_1") (pintype "passive"))
    )
    (net (code "34") (name "Net-(S4_2-O)") (class "Default")
      (node (ref "DIODE_GATE_4_2") (pin "A") (pinfunction "A_A") (pintype "passive"))
      (node (ref "S4_2") (pin "1") (pinfunction "O_1") (pintype "passive"))
    )
    (net (code "35") (name "Net-(S5_1-O)") (class "Default")
      (node (ref "DIODE_GATE_5_1") (pin "A") (pinfunction "A_A") (pintype "passive"))
      (node (ref "S5_1") (pin "1") (pinfunction "O_1") (pintype "passive"))
    )
    (net (code "36") (name "Net-(S5_2-O)") (class "Default")
      (node (ref "DIODE_GATE_5_2") (pin "A") (pinfunction "A_A") (pintype "passive"))
      (node (ref "S5_2") (pin "1") (pinfunction "O_1") (pintype "passive"))
    )
    (net (code "37") (name "Net-(S6_1-O)") (class "Default")
      (node (ref "DIODE_GATE_6_1") (pin "A") (pinfunction "A_A") (pintype "passive"))
      (node (ref "S6_1") (pin "1") (pinfunction "O_1") (pintype "passive"))
    )
    (net (code "38") (name "Net-(S6_2-O)") (class "Default")
      (node (ref "DIODE_GATE_6_2") (pin "A") (pinfunction "A_A") (pintype "passive"))
      (node (ref "S6_2") (pin "1") (pinfunction "O_1") (pintype "passive"))
    )
    (net (code "39") (name "Net-(S7_1-O)") (class "Default")
      (node (ref "DIODE_GATE_7_1") (pin "A") (pinfunction "A_A") (pintype "passive"))
      (node (ref "S7_1") (pin "1") (pinfunction "O_1") (pintype "passive"))
    )
    (net (code "40") (name "Net-(S7_2-O)") (class "Default")
      (node (ref "DIODE_GATE_7_2") (pin "A") (pinfunction "A_A") (pintype "passive"))
      (node (ref "S7_2") (pin "1") (pinfunction "O_1") (pintype "passive"))
    )
    (net (code "41") (name "Net-(S8_1-O)") (class "Default")
      (node (ref "DIODE_GATE_8_1") (pin "A") (pinfunction "A_A") (pintype "passive"))
      (node (ref "S8_1") (pin "1") (pinfunction "O_1") (pintype "passive"))
    )
    (net (code "42") (name "Net-(S8_2-O)") (class "Default")
      (node (ref "DIODE_GATE_8_2") (pin "A") (pinfunction "A_A") (pintype "passive"))
      (node (ref "S8_2") (pin "1") (pinfunction "O_1") (pintype "passive"))
    )
    (net (code "43") (name "unconnected-(GATE_OUT_1-NORM-Pad2)") (class "Default")
      (node (ref "GATE_OUT_1") (pin "2") (pinfunction "NORM_2") (pintype "bidirectional"))
    )
    (net (code "44") (name "unconnected-(GATE_OUT_2-NORM-Pad2)") (class "Default")
      (node (ref "GATE_OUT_2") (pin "2") (pinfunction "NORM_2") (pintype "bidirectional"))
    )
    (net (code "45") (name "unconnected-(J_RSTIN_1-NORM-Pad2)") (class "Default")
      (node (ref "J_RSTIN_1") (pin "2") (pinfunction "NORM_2") (pintype "bidirectional"))
    )
    (net (code "46") (name "unconnected-(J_RSTIN_2-NORM-Pad2)") (class "Default")
      (node (ref "J_RSTIN_2") (pin "2") (pinfunction "NORM_2") (pintype "bidirectional"))
    )
    (net (code "47") (name "unconnected-(MUTE_SEQ_1_1-S-Pad3)") (class "Default")
      (node (ref "MUTE_SEQ_1_1") (pin "3") (pinfunction "S_3") (pintype "passive"))
    )
    (net (code "48") (name "unconnected-(MUTE_SEQ_1_2-S-Pad3)") (class "Default")
      (node (ref "MUTE_SEQ_1_2") (pin "3") (pinfunction "S_3") (pintype "passive"))
    )
  )
)
